# ESPArmedButton-1_0.net
KiCad netlist of a schematic drawn in EAGLE
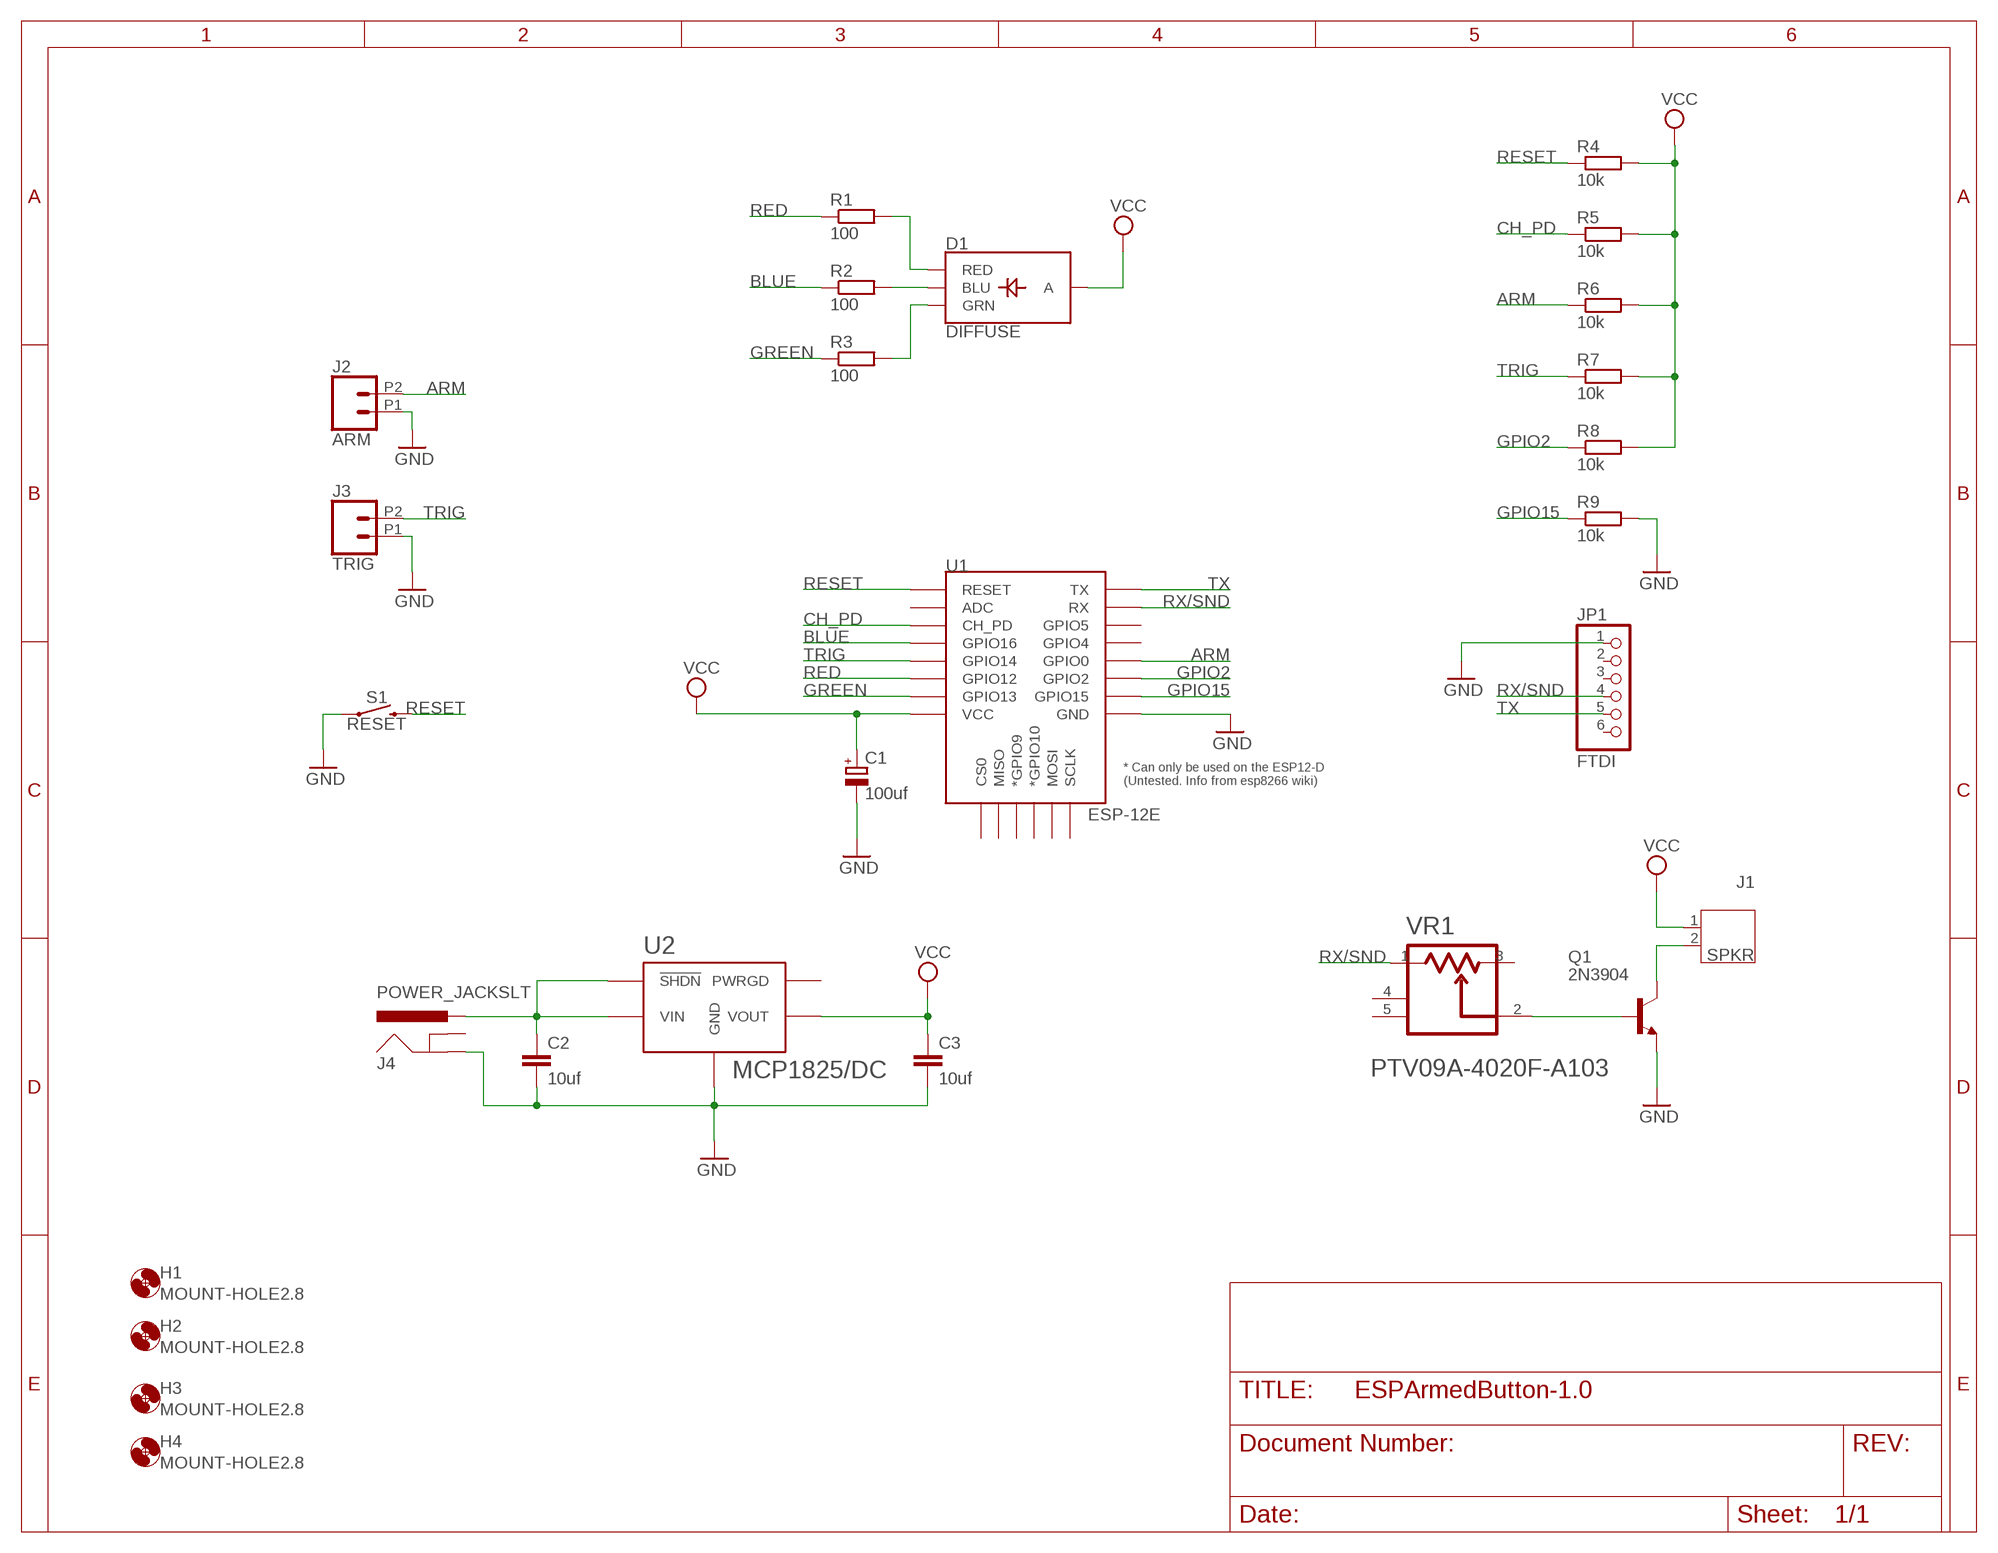
[diagram p0: schematic, sheet 1]

(export (version "E")
  (design (tool "Eeschema 10.0.6"))
  (components
    (comp (ref "C1")
      (value "100uf")
      (footprint "eagle-import:E2-5")
      (libsource (lib "eagle-import") (part "CPOL-EUE2-5"))
    )
    (comp (ref "C2")
      (value "10uf")
      (footprint "eagle-import:C050-025X075")
      (libsource (lib "eagle-import") (part "C-EU050-025X075"))
    )
    (comp (ref "C3")
      (value "10uf")
      (footprint "eagle-import:C050-025X075")
      (libsource (lib "eagle-import") (part "C-EU050-025X075"))
    )
    (comp (ref "D1")
      (value "DIFFUSE")
      (footprint "eagle-import:LED-RGB-THRU")
      (libsource (lib "eagle-import") (part "LED-RGB-CADIFFUSE"))
    )
    (comp (ref "H1")
      (value "MOUNT-HOLE2.8")
      (footprint "eagle-import:2,8")
      (libsource (lib "eagle-import") (part "MOUNT-HOLE2.8"))
    )
    (comp (ref "H2")
      (value "MOUNT-HOLE2.8")
      (footprint "eagle-import:2,8")
      (libsource (lib "eagle-import") (part "MOUNT-HOLE2.8"))
    )
    (comp (ref "H3")
      (value "MOUNT-HOLE2.8")
      (footprint "eagle-import:2,8")
      (libsource (lib "eagle-import") (part "MOUNT-HOLE2.8"))
    )
    (comp (ref "H4")
      (value "MOUNT-HOLE2.8")
      (footprint "eagle-import:2,8")
      (libsource (lib "eagle-import") (part "MOUNT-HOLE2.8"))
    )
    (comp (ref "J1")
      (value "SPKR")
      (footprint "eagle-import:JST-PH2")
      (libsource (lib "eagle-import") (part "JST-PH2"))
    )
    (comp (ref "J2")
      (value "ARM")
      (footprint "eagle-import:1X02_2.54_SCREWTERM")
      (libsource (lib "eagle-import") (part "CONN_022.54MM_SCREWTERM"))
    )
    (comp (ref "J3")
      (value "TRIG")
      (footprint "eagle-import:1X02_2.54_SCREWTERM")
      (libsource (lib "eagle-import") (part "CONN_022.54MM_SCREWTERM"))
    )
    (comp (ref "J4")
      (value "POWER_JACKSLT")
      (footprint "eagle-import:POWER_JACK_SLOT")
      (libsource (lib "eagle-import") (part "POWER_JACKSLT"))
    )
    (comp (ref "JP1")
      (value "FTDI")
      (footprint "eagle-import:1X06_90")
      (libsource (lib "eagle-import") (part "PINHD-1X6/90"))
    )
    (comp (ref "Q1")
      (value "2N3904")
      (footprint "eagle-import:TO92")
      (libsource (lib "eagle-import") (part "2N3904"))
    )
    (comp (ref "R1")
      (value "100")
      (footprint "eagle-import:0207_7")
      (libsource (lib "eagle-import") (part "R-EU_0207/7"))
    )
    (comp (ref "R2")
      (value "100")
      (footprint "eagle-import:0207_7")
      (libsource (lib "eagle-import") (part "R-EU_0207/7"))
    )
    (comp (ref "R3")
      (value "100")
      (footprint "eagle-import:0207_7")
      (libsource (lib "eagle-import") (part "R-EU_0207/7"))
    )
    (comp (ref "R4")
      (value "10k")
      (footprint "eagle-import:0207_7")
      (libsource (lib "eagle-import") (part "R-EU_0207/7"))
    )
    (comp (ref "R5")
      (value "10k")
      (footprint "eagle-import:0207_7")
      (libsource (lib "eagle-import") (part "R-EU_0207/7"))
    )
    (comp (ref "R6")
      (value "10k")
      (footprint "eagle-import:0207_7")
      (libsource (lib "eagle-import") (part "R-EU_0207/7"))
    )
    (comp (ref "R7")
      (value "10k")
      (footprint "eagle-import:0207_7")
      (libsource (lib "eagle-import") (part "R-EU_0207/7"))
    )
    (comp (ref "R8")
      (value "10k")
      (footprint "eagle-import:0207_7")
      (libsource (lib "eagle-import") (part "R-EU_0207/7"))
    )
    (comp (ref "R9")
      (value "10k")
      (footprint "eagle-import:0207_7")
      (libsource (lib "eagle-import") (part "R-EU_0207/7"))
    )
    (comp (ref "S1")
      (value "RESET")
      (footprint "eagle-import:TACTILE_SWITCH_PTH_6.0MM")
      (libsource (lib "eagle-import") (part "MOMENTARY-SWITCH-SPST-PTH-6.0MM"))
    )
    (comp (ref "U1")
      (value "ESP-12E")
      (footprint "eagle-import:ESP12E-SMD")
      (libsource (lib "eagle-import") (part "ESP12ESMD"))
    )
    (comp (ref "U2")
      (value "MCP1825/DC")
      (footprint "eagle-import:SOT-223-5")
      (libsource (lib "eagle-import") (part "MCP1825/DC"))
    )
    (comp (ref "VR1")
      (value "BOURNS_PTV09A-4020F-A103BOURNS_PTV09A-4020F-A103_0_0")
      (footprint "eagle-import:BOURNS_PTV09A-4020F-A103_0")
      (fields
        (field (name "DIGIKEY_PART_NUMBER") "PTV09A-4020F-A103-ND")
        (field (name "MF") "Bourns")
        (field (name "MOUSER_PART_NUMBER") "652-PTV09A-4020FA103")
      )
      (libsource (lib "eagle-import") (part "BOURNS_PTV09A-4020F-A103BOURNS_PTV09A-4020F-A103_0_0"))
    )
  )
  (nets
    (net (code "1") (name "/ARM") (class "Default")
      (node (ref "J2") (pin "P2") (pinfunction "2_P2") (pintype "passive"))
      (node (ref "R6") (pin "1") (pinfunction "1_1") (pintype "passive"))
      (node (ref "U1") (pin "GPIO0") (pinfunction "GPIO0_GPIO0") (pintype "bidirectional"))
    )
    (net (code "2") (name "/BLUE") (class "Default")
      (node (ref "R2") (pin "1") (pinfunction "1_1") (pintype "passive"))
      (node (ref "U1") (pin "GPIO16") (pinfunction "GPIO16_GPIO16") (pintype "bidirectional"))
    )
    (net (code "3") (name "/CH_PD") (class "Default")
      (node (ref "R5") (pin "1") (pinfunction "1_1") (pintype "passive"))
      (node (ref "U1") (pin "CH_PD") (pinfunction "CH_PD_CH_PD") (pintype "bidirectional"))
    )
    (net (code "4") (name "/GPIO2") (class "Default")
      (node (ref "R8") (pin "1") (pinfunction "1_1") (pintype "passive"))
      (node (ref "U1") (pin "GPIO2") (pinfunction "GPIO2_GPIO2") (pintype "bidirectional"))
    )
    (net (code "5") (name "/GPIO15") (class "Default")
      (node (ref "R9") (pin "1") (pinfunction "1_1") (pintype "passive"))
      (node (ref "U1") (pin "GPIO15") (pinfunction "GPIO15_GPIO15") (pintype "bidirectional"))
    )
    (net (code "6") (name "/GREEN") (class "Default")
      (node (ref "R3") (pin "1") (pinfunction "1_1") (pintype "passive"))
      (node (ref "U1") (pin "GPIO13") (pinfunction "GPIO13_GPIO13") (pintype "bidirectional"))
    )
    (net (code "7") (name "/RED") (class "Default")
      (node (ref "R1") (pin "1") (pinfunction "1_1") (pintype "passive"))
      (node (ref "U1") (pin "GPIO12") (pinfunction "GPIO12_GPIO12") (pintype "bidirectional"))
    )
    (net (code "8") (name "/RESET") (class "Default")
      (node (ref "R4") (pin "1") (pinfunction "1_1") (pintype "passive"))
      (node (ref "S1") (pin "3") (pinfunction "2_3") (pintype "passive"))
      (node (ref "U1") (pin "RESET") (pinfunction "RESET_RESET") (pintype "bidirectional"))
    )
    (net (code "9") (name "/RX{slash}SND") (class "Default")
      (node (ref "JP1") (pin "4") (pinfunction "4_4") (pintype "passive"))
      (node (ref "U1") (pin "RXD0") (pinfunction "RX_RXD0") (pintype "bidirectional"))
      (node (ref "VR1") (pin "1") (pinfunction "1_1") (pintype "bidirectional"))
    )
    (net (code "10") (name "/TRIG") (class "Default")
      (node (ref "J3") (pin "P2") (pinfunction "2_P2") (pintype "passive"))
      (node (ref "R7") (pin "1") (pinfunction "1_1") (pintype "passive"))
      (node (ref "U1") (pin "GPIO14") (pinfunction "GPIO14_GPIO14") (pintype "bidirectional"))
    )
    (net (code "11") (name "/TX") (class "Default")
      (node (ref "JP1") (pin "5") (pinfunction "5_5") (pintype "passive"))
      (node (ref "U1") (pin "TXD0") (pinfunction "TX_TXD0") (pintype "bidirectional"))
    )
    (net (code "12") (name "GND") (class "Default")
      (node (ref "C1") (pin "-") (pinfunction "-_-") (pintype "passive"))
      (node (ref "C2") (pin "2") (pinfunction "2_2") (pintype "passive"))
      (node (ref "C3") (pin "2") (pinfunction "2_2") (pintype "passive"))
      (node (ref "J2") (pin "P1") (pinfunction "1_P1") (pintype "passive"))
      (node (ref "J3") (pin "P1") (pinfunction "1_P1") (pintype "passive"))
      (node (ref "J4") (pin "GND@1") (pinfunction "GND_GND@1") (pintype "bidirectional"))
      (node (ref "JP1") (pin "1") (pinfunction "1_1") (pintype "passive"))
      (node (ref "Q1") (pin "3") (pinfunction "E_3") (pintype "passive"))
      (node (ref "R9") (pin "2") (pinfunction "2_2") (pintype "passive"))
      (node (ref "S1") (pin "1") (pinfunction "1_1") (pintype "passive"))
      (node (ref "U1") (pin "GND") (pinfunction "GND_GND") (pintype "bidirectional"))
      (node (ref "U2") (pin "P$3") (pinfunction "GND_P$3") (pintype "power_in"))
      (node (ref "U2") (pin "P$6") (pinfunction "GND_P$6") (pintype "power_in"))
    )
    (net (code "13") (name "Net-(D1-BLU)") (class "Default")
      (node (ref "D1") (pin "4") (pinfunction "BLU_4") (pintype "bidirectional"))
      (node (ref "R2") (pin "2") (pinfunction "2_2") (pintype "passive"))
    )
    (net (code "14") (name "Net-(D1-GRN)") (class "Default")
      (node (ref "D1") (pin "3") (pinfunction "GRN_3") (pintype "bidirectional"))
      (node (ref "R3") (pin "2") (pinfunction "2_2") (pintype "passive"))
    )
    (net (code "15") (name "Net-(D1-RED)") (class "Default")
      (node (ref "D1") (pin "1") (pinfunction "RED_1") (pintype "bidirectional"))
      (node (ref "R1") (pin "2") (pinfunction "2_2") (pintype "passive"))
    )
    (net (code "16") (name "Net-(Q1-B)") (class "Default")
      (node (ref "Q1") (pin "2") (pinfunction "B_2") (pintype "passive"))
      (node (ref "VR1") (pin "2") (pinfunction "2_2") (pintype "bidirectional"))
    )
    (net (code "17") (name "Net-(Q1-C)") (class "Default")
      (node (ref "J1") (pin "2") (pinfunction "2_2") (pintype "passive"))
      (node (ref "Q1") (pin "1") (pinfunction "C_1") (pintype "passive"))
    )
    (net (code "18") (name "Net-(U2-VIN)") (class "Default")
      (node (ref "C2") (pin "1") (pinfunction "1_1") (pintype "passive"))
      (node (ref "J4") (pin "PWR") (pinfunction "PWR_PWR") (pintype "bidirectional"))
      (node (ref "U2") (pin "P$1") (pinfunction "~{SHDN}_P$1") (pintype "input"))
      (node (ref "U2") (pin "P$2") (pinfunction "VIN_P$2") (pintype "power_in"))
    )
    (net (code "19") (name "VCC") (class "Default")
      (node (ref "C1") (pin "+") (pinfunction "+_+") (pintype "passive"))
      (node (ref "C3") (pin "1") (pinfunction "1_1") (pintype "passive"))
      (node (ref "D1") (pin "2") (pinfunction "A_2") (pintype "bidirectional"))
      (node (ref "J1") (pin "1") (pinfunction "1_1") (pintype "passive"))
      (node (ref "R4") (pin "2") (pinfunction "2_2") (pintype "passive"))
      (node (ref "R5") (pin "2") (pinfunction "2_2") (pintype "passive"))
      (node (ref "R6") (pin "2") (pinfunction "2_2") (pintype "passive"))
      (node (ref "R7") (pin "2") (pinfunction "2_2") (pintype "passive"))
      (node (ref "R8") (pin "2") (pinfunction "2_2") (pintype "passive"))
      (node (ref "U1") (pin "VCC") (pinfunction "VCC_VCC") (pintype "bidirectional"))
      (node (ref "U2") (pin "P$4") (pinfunction "VOUT_P$4") (pintype "power_in"))
    )
    (net (code "20") (name "unconnected-(J4-GNDBREAK-PadGND@2)") (class "Default")
      (node (ref "J4") (pin "GND@2") (pinfunction "GNDBREAK_GND@2") (pintype "bidirectional"))
    )
    (net (code "21") (name "unconnected-(JP1-Pad2)") (class "Default")
      (node (ref "JP1") (pin "2") (pinfunction "2_2") (pintype "passive"))
    )
    (net (code "22") (name "unconnected-(JP1-Pad3)") (class "Default")
      (node (ref "JP1") (pin "3") (pinfunction "3_3") (pintype "passive"))
    )
    (net (code "23") (name "unconnected-(JP1-Pad6)") (class "Default")
      (node (ref "JP1") (pin "6") (pinfunction "6_6") (pintype "passive"))
    )
    (net (code "24") (name "unconnected-(U1-*GPIO9-PadGPIO9)") (class "Default")
      (node (ref "U1") (pin "GPIO9") (pinfunction "*GPIO9_GPIO9") (pintype "bidirectional"))
    )
    (net (code "25") (name "unconnected-(U1-*GPIO10-PadGPIO10)") (class "Default")
      (node (ref "U1") (pin "GPIO10") (pinfunction "*GPIO10_GPIO10") (pintype "bidirectional"))
    )
    (net (code "26") (name "unconnected-(U1-PadADC)") (class "Default")
      (node (ref "U1") (pin "ADC") (pinfunction "ADC_ADC") (pintype "bidirectional"))
    )
    (net (code "27") (name "unconnected-(U1-PadCS0)") (class "Default")
      (node (ref "U1") (pin "CS0") (pinfunction "CS0_CS0") (pintype "bidirectional"))
    )
    (net (code "28") (name "unconnected-(U1-PadGPIO4)") (class "Default")
      (node (ref "U1") (pin "GPIO4") (pinfunction "GPIO4_GPIO4") (pintype "bidirectional"))
    )
    (net (code "29") (name "unconnected-(U1-PadGPIO5)") (class "Default")
      (node (ref "U1") (pin "GPIO5") (pinfunction "GPIO5_GPIO5") (pintype "bidirectional"))
    )
    (net (code "30") (name "unconnected-(U1-PadMISO)") (class "Default")
      (node (ref "U1") (pin "MISO") (pinfunction "MISO_MISO") (pintype "bidirectional"))
    )
    (net (code "31") (name "unconnected-(U1-PadMOSI)") (class "Default")
      (node (ref "U1") (pin "MOSI") (pinfunction "MOSI_MOSI") (pintype "bidirectional"))
    )
    (net (code "32") (name "unconnected-(U1-PadSCLK)") (class "Default")
      (node (ref "U1") (pin "SCLK") (pinfunction "SCLK_SCLK") (pintype "bidirectional"))
    )
    (net (code "33") (name "unconnected-(U2-PWRGD-PadP$5)") (class "Default")
      (node (ref "U2") (pin "P$5") (pinfunction "PWRGD_P$5") (pintype "output"))
    )
    (net (code "34") (name "unconnected-(VR1-MNT_1-Pad4)") (class "Default")
      (node (ref "VR1") (pin "4") (pinfunction "MNT_1_4") (pintype "bidirectional"))
    )
    (net (code "35") (name "unconnected-(VR1-MNT_2-Pad5)") (class "Default")
      (node (ref "VR1") (pin "5") (pinfunction "MNT_2_5") (pintype "bidirectional"))
    )
    (net (code "36") (name "unconnected-(VR1-Pad3)") (class "Default")
      (node (ref "VR1") (pin "3") (pinfunction "3_3") (pintype "bidirectional"))
    )
  )
)
